# Morpheus_pill.net
KiCad netlist of a schematic drawn in Altium Designer
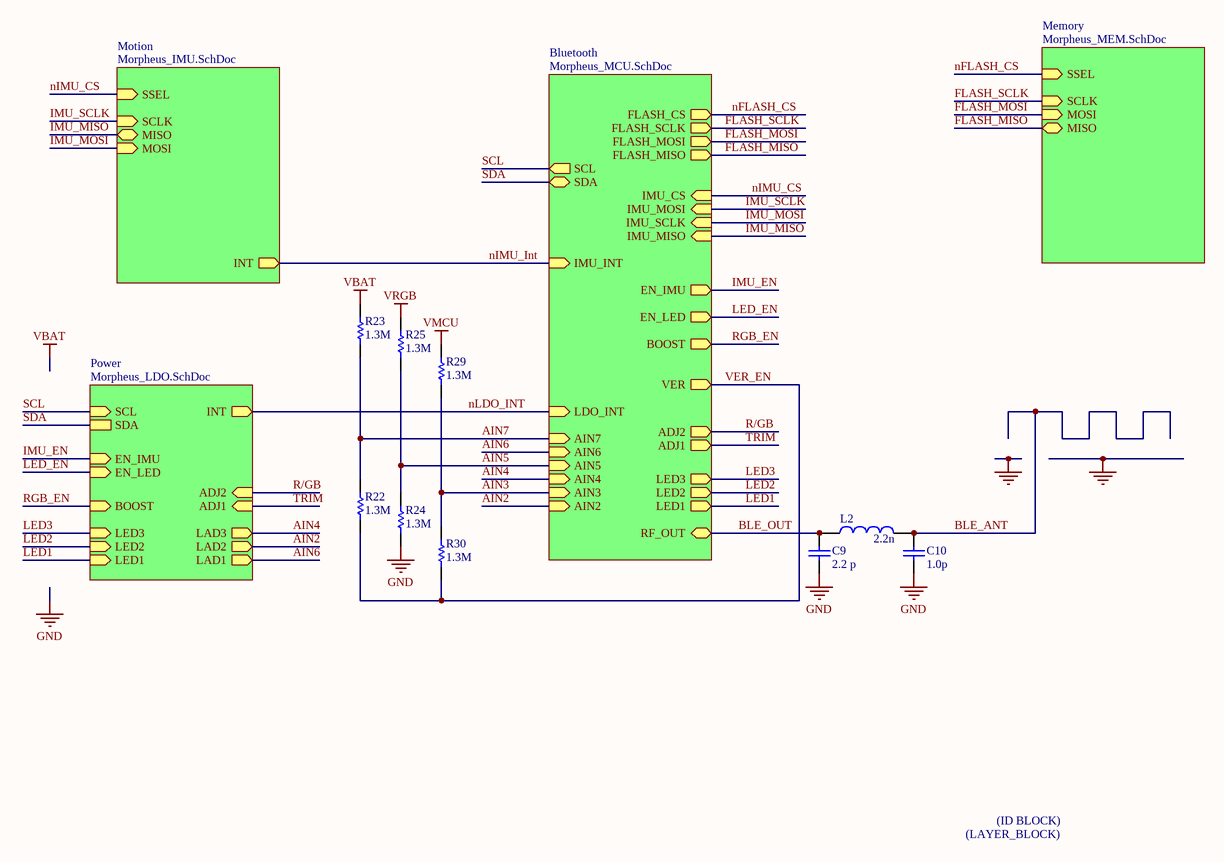
[diagram p0: Morpheus_pill.SchDoc]

(export (version "E")
  (design (tool "Eeschema 10.0.6"))
  (components
    (comp (ref "*")
      (value "LAYER_BLOCK")
      (footprint "Layer Stackup")
      (libsource (lib "Hello") (part "LAYER_BLOCK"))
    )
    (comp (ref "C9")
      (value "2.2 p")
      (footprint "CAP0402")
      (description "Chip capacitor")
      (fields (field (name "TOLERANCE") "0.05") (field (name "VOLTAGE") "50 V"))
      (libsource (lib "Hello") (part "C_2.2p_0.05_50_C0G_0402"))
    )
    (comp (ref "C10")
      (value "1.0p")
      (footprint "CAP0402")
      (description "Chip capacitor")
      (fields (field (name "TOLERANCE") "5 %") (field (name "VOLTAGE") "16V"))
      (libsource (lib "Hello") (part "C_2200p_5_16_STD_0402"))
    )
    (comp (ref "ID1") (value "ID_BLOCK") (footprint "Hello Band") (libsource (lib "Hello") (part "ID_BLOCK")))
    (comp (ref "L2")
      (value "2.2n")
      (footprint "IND_0402")
      (description "SMD power inductor, 2.2uH")
      (fields (field (name "TOLERANCE") "0.1"))
      (libsource (lib "Hello") (part "L_2.2n_0.1_?_0.150_0.9_?"))
    )
    (comp (ref "R22")
      (value "1.3M")
      (footprint "RES0402")
      (description "Chip Resistor")
      (fields (field (name "TOLERANCE") "5 %") (field (name "POWER") "0.1 W"))
      (libsource (lib "Hello") (part "R_1.3M_5_0.1_0402_1"))
    )
    (comp (ref "R23")
      (value "1.3M")
      (footprint "RES0402")
      (description "Chip Resistor")
      (fields (field (name "TOLERANCE") "5 %") (field (name "POWER") "0.1 W"))
      (libsource (lib "Hello") (part "R_1.3M_5_0.1_0402_1"))
    )
    (comp (ref "R24")
      (value "1.3M")
      (footprint "RES0402")
      (description "Chip Resistor")
      (fields (field (name "TOLERANCE") "5 %") (field (name "POWER") "0.1 W"))
      (libsource (lib "Hello") (part "R_1.3M_5_0.1_0402_1"))
    )
    (comp (ref "R25")
      (value "1.3M")
      (footprint "RES0402")
      (description "Chip Resistor")
      (fields (field (name "TOLERANCE") "5 %") (field (name "POWER") "0.1 W"))
      (libsource (lib "Hello") (part "R_1.3M_5_0.1_0402_1"))
    )
    (comp (ref "R29")
      (value "1.3M")
      (footprint "RES0402")
      (description "Chip Resistor")
      (fields (field (name "TOLERANCE") "5 %") (field (name "POWER") "0.1 W"))
      (libsource (lib "Hello") (part "R_1.3M_5_0.1_0402_1"))
    )
    (comp (ref "R30")
      (value "1.3M")
      (footprint "RES0402")
      (description "Chip Resistor")
      (fields (field (name "TOLERANCE") "5 %") (field (name "POWER") "0.1 W"))
      (libsource (lib "Hello") (part "R_1.3M_5_0.1_0402_1"))
    )
  )
  (nets
    (net (code "2") (name "/AIN3") (class "Default")
      (node (ref "R29") (pin "1") (pinfunction "1_1") (pintype "passive"))
      (node (ref "R30") (pin "2") (pinfunction "2_2") (pintype "passive"))
    )
    (net (code "4") (name "/AIN5") (class "Default")
      (node (ref "R24") (pin "2") (pinfunction "2_2") (pintype "passive"))
      (node (ref "R25") (pin "1") (pinfunction "1_1") (pintype "passive"))
    )
    (net (code "6") (name "/AIN7") (class "Default")
      (node (ref "R22") (pin "2") (pinfunction "2_2") (pintype "passive"))
      (node (ref "R23") (pin "1") (pinfunction "1_1") (pintype "passive"))
    )
    (net (code "7") (name "/BLE_ANT") (class "Default")
      (node (ref "C10") (pin "1") (pinfunction "1_1") (pintype "passive"))
      (node (ref "L2") (pin "2") (pintype "passive"))
    )
    (net (code "8") (name "/BLE_OUT") (class "Default")
      (node (ref "C9") (pin "1") (pinfunction "1_1") (pintype "passive"))
      (node (ref "L2") (pin "1") (pintype "passive"))
    )
    (net (code "25") (name "/VER_EN") (class "Default")
      (node (ref "R22") (pin "1") (pinfunction "1_1") (pintype "passive"))
      (node (ref "R30") (pin "1") (pinfunction "1_1") (pintype "passive"))
    )
    (net (code "30") (name "GND") (class "Default")
      (node (ref "C10") (pin "2") (pinfunction "2_2") (pintype "passive"))
      (node (ref "C9") (pin "2") (pinfunction "2_2") (pintype "passive"))
      (node (ref "R24") (pin "1") (pinfunction "1_1") (pintype "passive"))
    )
    (net (code "31") (name "VBAT") (class "Default")
      (node (ref "R23") (pin "2") (pinfunction "2_2") (pintype "passive"))
    )
    (net (code "32") (name "VMCU") (class "Default")
      (node (ref "R29") (pin "2") (pinfunction "2_2") (pintype "passive"))
    )
    (net (code "33") (name "VRGB") (class "Default")
      (node (ref "R25") (pin "2") (pinfunction "2_2") (pintype "passive"))
    )
  )
)
